# AmpliHugo.net
KiCad netlist of a schematic drawn in Altium Designer
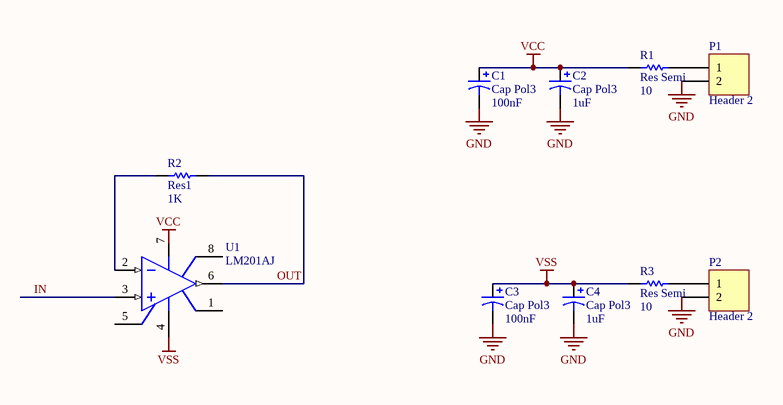
[diagram p0: AmpliHugo.SchDoc]

(export (version "E")
  (design (tool "Eeschema 10.0.6"))
  (components
    (comp (ref "C1")
      (value "Cap Pol3")
      (footprint "C0805")
      (description "Polarized Capacitor (Surface Mount)")
      (fields (field (name "ALTIUM_VALUE") "100nF") (field (name "PUBLISHER") "Altium Limited"))
      (libsource (lib "Miscellaneous Devices") (part "Cap Pol3"))
    )
    (comp (ref "C2")
      (value "Cap Pol3")
      (footprint "C0805")
      (description "Polarized Capacitor (Surface Mount)")
      (fields (field (name "ALTIUM_VALUE") "1uF") (field (name "PUBLISHER") "Altium Limited"))
      (libsource (lib "Miscellaneous Devices") (part "Cap Pol3"))
    )
    (comp (ref "C3")
      (value "Cap Pol3")
      (footprint "C0805")
      (description "Polarized Capacitor (Surface Mount)")
      (fields (field (name "ALTIUM_VALUE") "100nF") (field (name "PUBLISHER") "Altium Limited"))
      (libsource (lib "Miscellaneous Devices") (part "Cap Pol3"))
    )
    (comp (ref "C4")
      (value "Cap Pol3")
      (footprint "C0805")
      (description "Polarized Capacitor (Surface Mount)")
      (fields (field (name "ALTIUM_VALUE") "1uF") (field (name "PUBLISHER") "Altium Limited"))
      (libsource (lib "Miscellaneous Devices") (part "Cap Pol3"))
    )
    (comp (ref "P1")
      (value "Header 2")
      (footprint "HDR1X2")
      (description "Header, 2-Pin")
      (fields (field (name "PUBLISHER") "Altium Limited"))
      (libsource (lib "Miscellaneous Connectors") (part "Header 2"))
    )
    (comp (ref "P2")
      (value "Header 2")
      (footprint "HDR1X2")
      (description "Header, 2-Pin")
      (fields (field (name "PUBLISHER") "Altium Limited"))
      (libsource (lib "Miscellaneous Connectors") (part "Header 2"))
    )
    (comp (ref "R1")
      (value "Res Semi")
      (footprint "2012[0805]")
      (description "Semiconductor Resistor")
      (fields (field (name "ALTIUM_VALUE") "10") (field (name "PUBLISHER") "Altium Limited"))
      (libsource (lib "Miscellaneous Devices") (part "Res Semi"))
    )
    (comp (ref "R2")
      (value "Res1")
      (footprint "AXIAL-0.3")
      (description "Resistor")
      (fields (field (name "ALTIUM_VALUE") "1K") (field (name "PUBLISHER") "Altium Limited"))
      (libsource (lib "Miscellaneous Devices") (part "Res1"))
    )
    (comp (ref "R3")
      (value "Res Semi")
      (footprint "2012[0805]")
      (description "Semiconductor Resistor")
      (fields (field (name "ALTIUM_VALUE") "10") (field (name "PUBLISHER") "Altium Limited"))
      (libsource (lib "Miscellaneous Devices") (part "Res Semi"))
    )
    (comp (ref "U1")
      (value "LM201AJ")
      (footprint "693-02")
      (description "General-Purpose Adjustable Operational Amplifier")
      (fields (field (name "PUBLISHER") "Altium Limited"))
      (libsource (lib "Motorola Amplifier Operational Amplifier") (part "LM201AJ"))
    )
  )
  (nets
    (net (code "1") (name "/IN") (class "Default")
      (node (ref "U1") (pin "3") (pinfunction "IN+_3") (pintype "input"))
    )
    (net (code "2") (name "/OUT") (class "Default")
      (node (ref "R2") (pin "2") (pinfunction "2_2") (pintype "passive"))
      (node (ref "U1") (pin "6") (pinfunction "OUT_6") (pintype "output"))
    )
    (net (code "3") (name "GND") (class "Default")
      (node (ref "C1") (pin "2") (pinfunction "2_2") (pintype "passive"))
      (node (ref "C2") (pin "2") (pinfunction "2_2") (pintype "passive"))
      (node (ref "C3") (pin "2") (pinfunction "2_2") (pintype "passive"))
      (node (ref "C4") (pin "2") (pinfunction "2_2") (pintype "passive"))
      (node (ref "P1") (pin "2") (pinfunction "2_2") (pintype "passive"))
      (node (ref "P2") (pin "2") (pinfunction "2_2") (pintype "passive"))
    )
    (net (code "4") (name "Net-(P1-Pad1)") (class "Default")
      (node (ref "P1") (pin "1") (pinfunction "1_1") (pintype "passive"))
      (node (ref "R1") (pin "2") (pinfunction "2_2") (pintype "passive"))
    )
    (net (code "5") (name "Net-(P2-Pad1)") (class "Default")
      (node (ref "P2") (pin "1") (pinfunction "1_1") (pintype "passive"))
      (node (ref "R3") (pin "2") (pinfunction "2_2") (pintype "passive"))
    )
    (net (code "6") (name "Net-(U1-IN-)") (class "Default")
      (node (ref "R2") (pin "1") (pinfunction "1_1") (pintype "passive"))
      (node (ref "U1") (pin "2") (pinfunction "IN-_2") (pintype "input"))
    )
    (net (code "7") (name "VCC") (class "Default")
      (node (ref "C1") (pin "1") (pinfunction "1_1") (pintype "passive"))
      (node (ref "C2") (pin "1") (pinfunction "1_1") (pintype "passive"))
      (node (ref "R1") (pin "1") (pinfunction "1_1") (pintype "passive"))
    )
    (net (code "8") (name "VSS") (class "Default")
      (node (ref "C3") (pin "1") (pinfunction "1_1") (pintype "passive"))
      (node (ref "C4") (pin "1") (pinfunction "1_1") (pintype "passive"))
      (node (ref "R3") (pin "1") (pinfunction "1_1") (pintype "passive"))
      (node (ref "U1") (pin "4") (pinfunction "V-_4") (pintype "power_in"))
    )
    (net (code "9") (name "unconnected-(U1-BAL-Pad1)") (class "Default")
      (node (ref "U1") (pin "1") (pinfunction "BAL_1") (pintype "passive"))
    )
    (net (code "10") (name "unconnected-(U1-BAL-Pad5)") (class "Default")
      (node (ref "U1") (pin "5") (pinfunction "BAL_5") (pintype "passive"))
    )
    (net (code "11") (name "unconnected-(U1-CMPEN-Pad8)") (class "Default")
      (node (ref "U1") (pin "8") (pinfunction "CMPEN_8") (pintype "passive"))
    )
    (net (code "12") (name "unconnected-(U1-V+-Pad7)") (class "Default")
      (node (ref "U1") (pin "7") (pinfunction "V+_7") (pintype "power_in"))
    )
  )
)
